# mainboard.net
KiCad netlist of a schematic drawn in Altium Designer
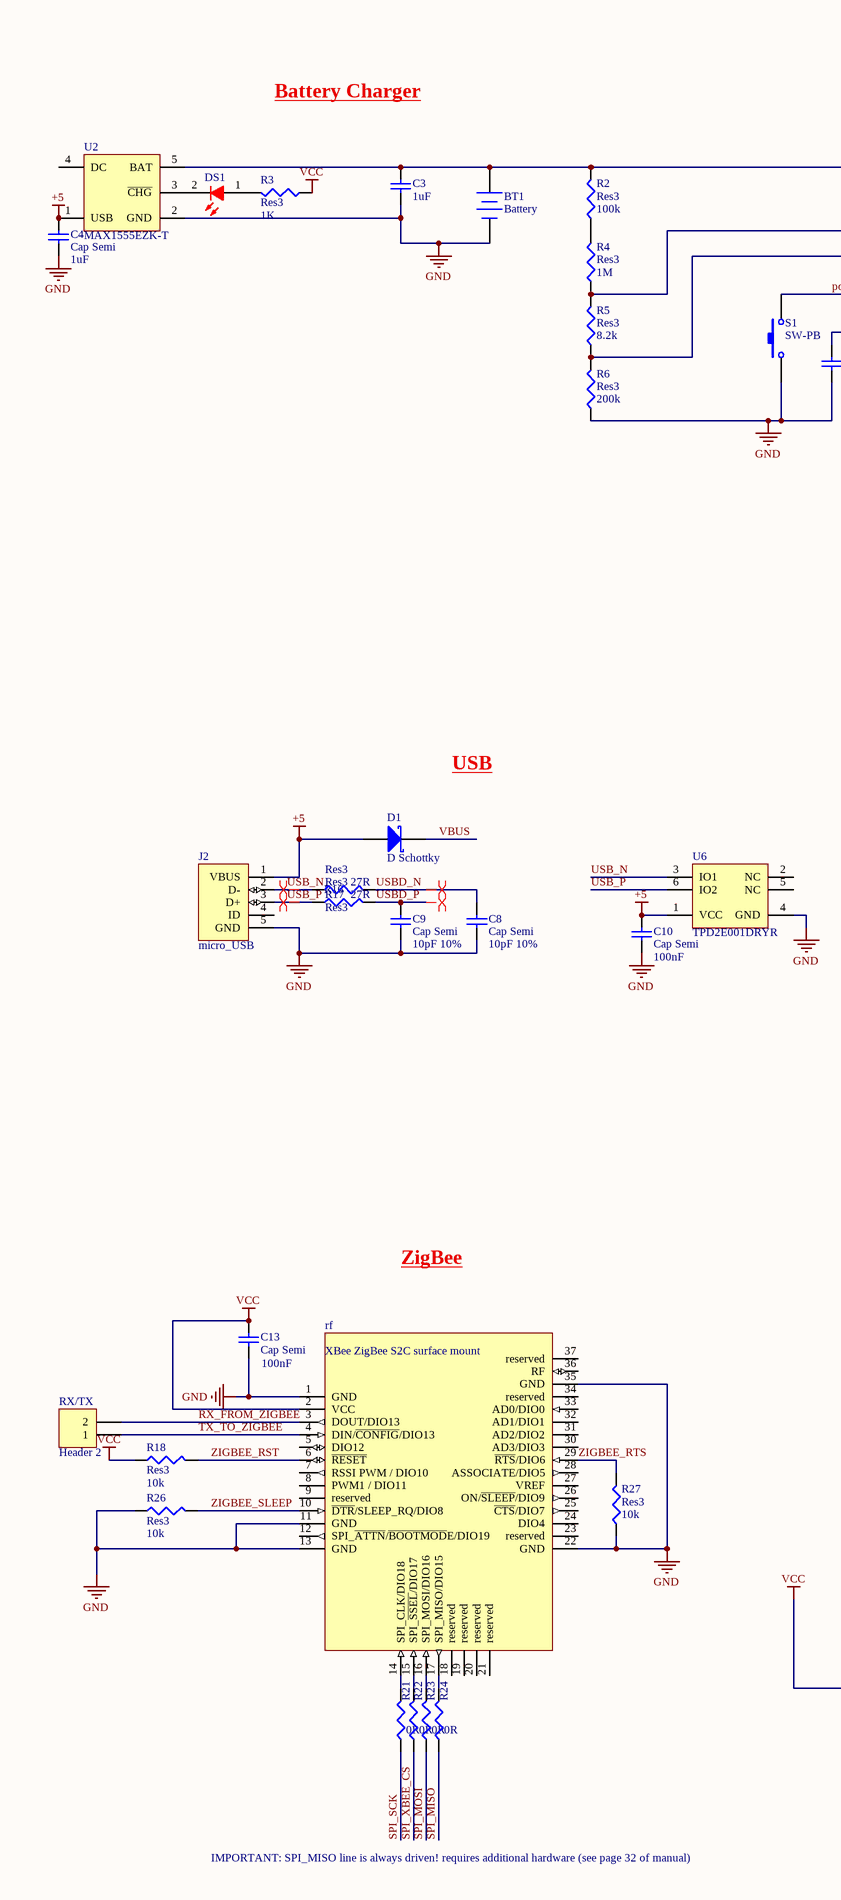
[diagram p0: mainboard.SchDoc, left]
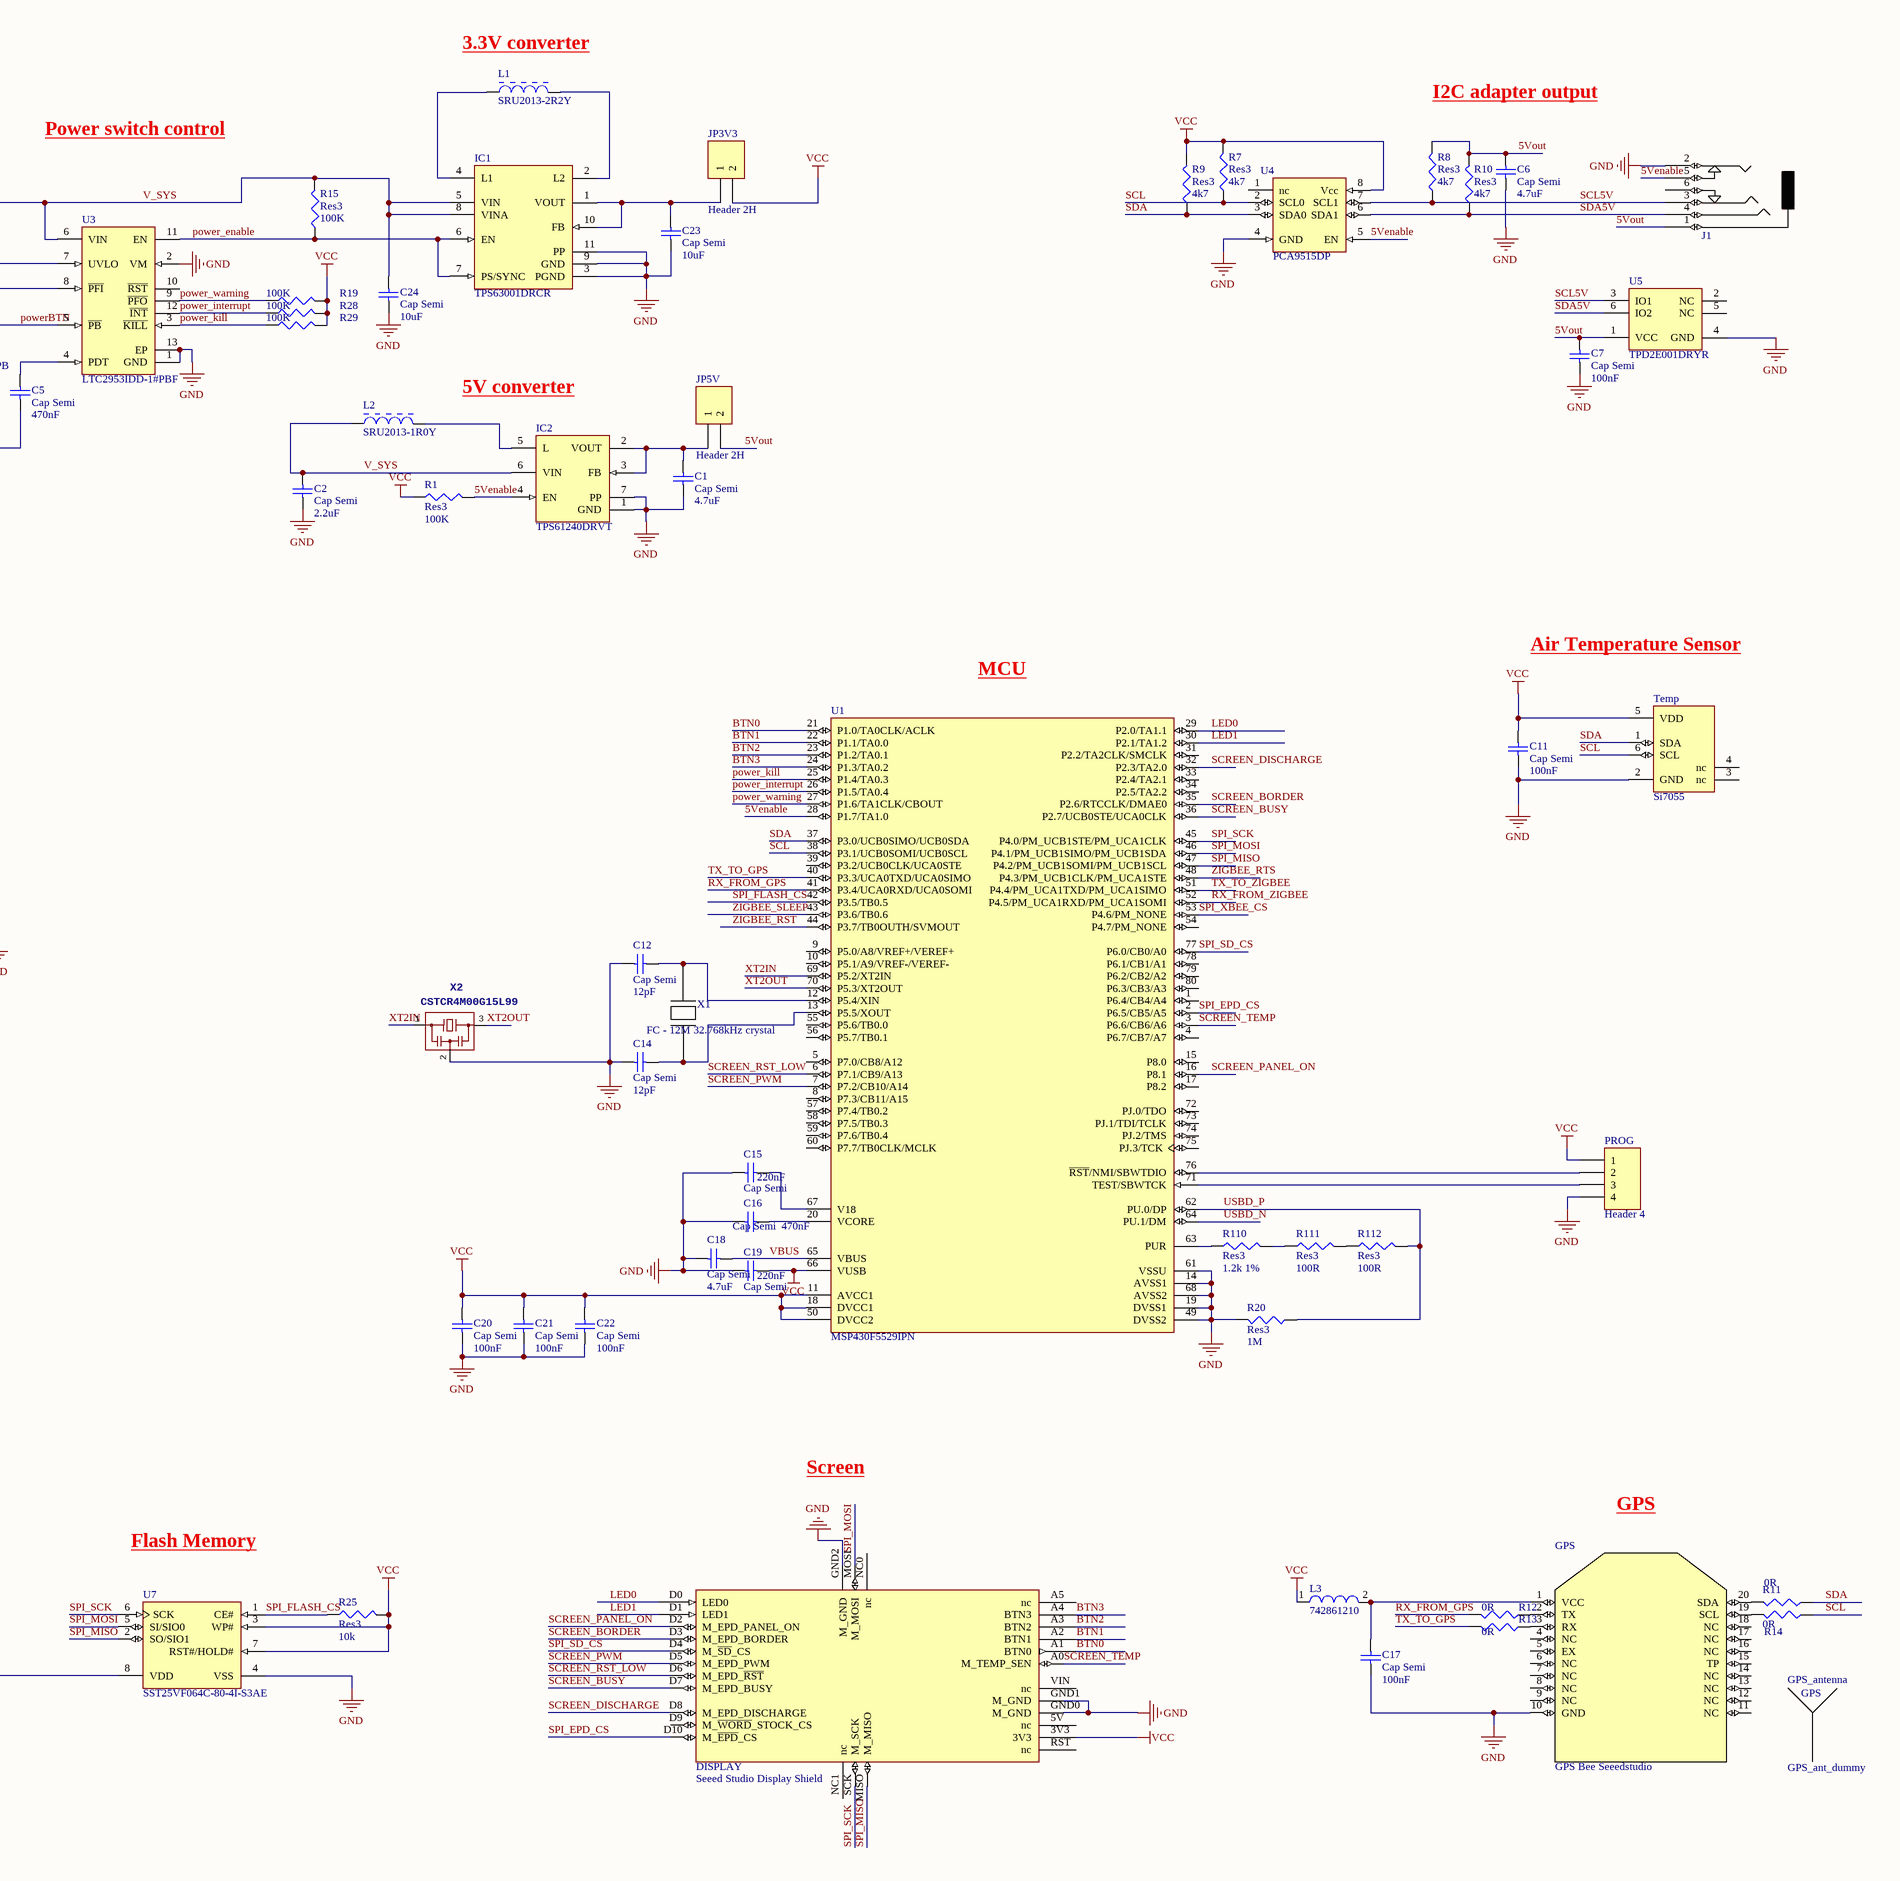
[diagram p1: mainboard.SchDoc, right]

(export (version "E")
  (design (tool "Eeschema 10.0.6"))
  (components
    (comp (ref "BT1")
      (value "Battery")
      (footprint "BAT-2")
      (description "Multicell Battery")
      (fields (field (name "PUBLISHER") "Altium Limited"))
      (libsource (lib "Miscellaneous Devices") (part "Battery"))
    )
    (comp (ref "C1")
      (value "Cap Semi")
      (footprint "1608[0603]")
      (description "Capacitor (Semiconductor SIM Model)")
      (fields (field (name "ALTIUM_VALUE") "4.7uF") (field (name "PUBLISHER") "Altium Limited"))
      (libsource (lib "Miscellaneous Devices") (part "Cap Semi"))
    )
    (comp (ref "C2")
      (value "Cap Semi")
      (footprint "1608[0603]")
      (description "Capacitor (Semiconductor SIM Model)")
      (fields (field (name "ALTIUM_VALUE") "2.2uF") (field (name "PUBLISHER") "Altium Limited"))
      (libsource (lib "Miscellaneous Devices") (part "Cap Semi"))
    )
    (comp (ref "C3")
      (value "1uF")
      (footprint "1608[0603]")
      (description "Capacitor (Semiconductor SIM Model)")
      (fields (field (name "Comment") "Cap Semi") (field (name "PUBLISHER") "Altium Limited"))
      (libsource (lib "Miscellaneous Devices") (part "Cap Semi"))
    )
    (comp (ref "C4")
      (value "Cap Semi")
      (footprint "1608[0603]")
      (description "Capacitor (Semiconductor SIM Model)")
      (fields (field (name "ALTIUM_VALUE") "1uF") (field (name "PUBLISHER") "Altium Limited"))
      (libsource (lib "Miscellaneous Devices") (part "Cap Semi"))
    )
    (comp (ref "C5")
      (value "Cap Semi")
      (footprint "1608[0603]")
      (description "Capacitor (Semiconductor SIM Model)")
      (fields (field (name "ALTIUM_VALUE") "470nF") (field (name "PUBLISHER") "Altium Limited"))
      (libsource (lib "Miscellaneous Devices") (part "Cap Semi"))
    )
    (comp (ref "C6")
      (value "Cap Semi")
      (footprint "1608[0603]")
      (description "Capacitor (Semiconductor SIM Model)")
      (fields (field (name "ALTIUM_VALUE") "4.7uF") (field (name "PUBLISHER") "Altium Limited"))
      (libsource (lib "Miscellaneous Devices") (part "Cap Semi"))
    )
    (comp (ref "C7")
      (value "Cap Semi")
      (footprint "1608[0603]")
      (description "Capacitor (Semiconductor SIM Model)")
      (fields (field (name "ALTIUM_VALUE") "100nF") (field (name "PUBLISHER") "Altium Limited"))
      (libsource (lib "Miscellaneous Devices") (part "Cap Semi"))
    )
    (comp (ref "C8")
      (value "Cap Semi")
      (footprint "1608[0603]")
      (description "Capacitor (Semiconductor SIM Model)")
      (fields (field (name "ALTIUM_VALUE") "10pF 10%") (field (name "PUBLISHER") "Altium Limited"))
      (libsource (lib "Miscellaneous Devices") (part "Cap Semi"))
    )
    (comp (ref "C9")
      (value "Cap Semi")
      (footprint "1608[0603]")
      (description "Capacitor (Semiconductor SIM Model)")
      (fields (field (name "ALTIUM_VALUE") "10pF 10%") (field (name "PUBLISHER") "Altium Limited"))
      (libsource (lib "Miscellaneous Devices") (part "Cap Semi"))
    )
    (comp (ref "C10")
      (value "Cap Semi")
      (footprint "1608[0603]")
      (description "Capacitor (Semiconductor SIM Model)")
      (fields (field (name "ALTIUM_VALUE") "100nF") (field (name "PUBLISHER") "Altium Limited"))
      (libsource (lib "Miscellaneous Devices") (part "Cap Semi"))
    )
    (comp (ref "C11")
      (value "Cap Semi")
      (footprint "1608[0603]")
      (description "Capacitor (Semiconductor SIM Model)")
      (fields (field (name "ALTIUM_VALUE") "100nF") (field (name "PUBLISHER") "Altium Limited"))
      (libsource (lib "Miscellaneous Devices") (part "Cap Semi"))
    )
    (comp (ref "C12")
      (value "Cap Semi")
      (footprint "1608[0603]")
      (description "Capacitor (Semiconductor SIM Model)")
      (fields (field (name "ALTIUM_VALUE") "12pF") (field (name "PUBLISHER") "Altium Limited"))
      (libsource (lib "Miscellaneous Devices") (part "Cap Semi"))
    )
    (comp (ref "C13")
      (value "Cap Semi")
      (footprint "1608[0603]")
      (description "Capacitor (Semiconductor SIM Model)")
      (fields (field (name "ALTIUM_VALUE") "100nF") (field (name "PUBLISHER") "Altium Limited"))
      (libsource (lib "Miscellaneous Devices") (part "Cap Semi"))
    )
    (comp (ref "C14")
      (value "Cap Semi")
      (footprint "1608[0603]")
      (description "Capacitor (Semiconductor SIM Model)")
      (fields (field (name "ALTIUM_VALUE") "12pF") (field (name "PUBLISHER") "Altium Limited"))
      (libsource (lib "Miscellaneous Devices") (part "Cap Semi"))
    )
    (comp (ref "C15")
      (value "Cap Semi")
      (footprint "1608[0603]")
      (description "Capacitor (Semiconductor SIM Model)")
      (fields (field (name "ALTIUM_VALUE") "220nF") (field (name "PUBLISHER") "Altium Limited"))
      (libsource (lib "Miscellaneous Devices") (part "Cap Semi"))
    )
    (comp (ref "C16")
      (value "Cap Semi")
      (footprint "1608[0603]")
      (description "Capacitor (Semiconductor SIM Model)")
      (fields (field (name "ALTIUM_VALUE") "470nF") (field (name "PUBLISHER") "Altium Limited"))
      (libsource (lib "Miscellaneous Devices") (part "Cap Semi"))
    )
    (comp (ref "C17")
      (value "Cap Semi")
      (footprint "1608[0603]")
      (description "Capacitor (Semiconductor SIM Model)")
      (fields (field (name "ALTIUM_VALUE") "100nF") (field (name "PUBLISHER") "Altium Limited"))
      (libsource (lib "Miscellaneous Devices") (part "Cap Semi"))
    )
    (comp (ref "C18")
      (value "Cap Semi")
      (footprint "1608[0603]")
      (description "Capacitor (Semiconductor SIM Model)")
      (fields (field (name "ALTIUM_VALUE") "4.7uF") (field (name "PUBLISHER") "Altium Limited"))
      (libsource (lib "Miscellaneous Devices") (part "Cap Semi"))
    )
    (comp (ref "C19")
      (value "Cap Semi")
      (footprint "1608[0603]")
      (description "Capacitor (Semiconductor SIM Model)")
      (fields (field (name "ALTIUM_VALUE") "220nF") (field (name "PUBLISHER") "Altium Limited"))
      (libsource (lib "Miscellaneous Devices") (part "Cap Semi"))
    )
    (comp (ref "C20")
      (value "Cap Semi")
      (footprint "1608[0603]")
      (description "Capacitor (Semiconductor SIM Model)")
      (fields (field (name "ALTIUM_VALUE") "100nF") (field (name "PUBLISHER") "Altium Limited"))
      (libsource (lib "Miscellaneous Devices") (part "Cap Semi"))
    )
    (comp (ref "C21")
      (value "Cap Semi")
      (footprint "1608[0603]")
      (description "Capacitor (Semiconductor SIM Model)")
      (fields (field (name "ALTIUM_VALUE") "100nF") (field (name "PUBLISHER") "Altium Limited"))
      (libsource (lib "Miscellaneous Devices") (part "Cap Semi"))
    )
    (comp (ref "C22")
      (value "Cap Semi")
      (footprint "1608[0603]")
      (description "Capacitor (Semiconductor SIM Model)")
      (fields (field (name "ALTIUM_VALUE") "100nF") (field (name "PUBLISHER") "Altium Limited"))
      (libsource (lib "Miscellaneous Devices") (part "Cap Semi"))
    )
    (comp (ref "C23")
      (value "Cap Semi")
      (footprint "C1206")
      (description "Capacitor (Semiconductor SIM Model)")
      (fields (field (name "ALTIUM_VALUE") "10uF") (field (name "PUBLISHER") "Altium Limited"))
      (libsource (lib "Miscellaneous Devices") (part "Cap Semi"))
    )
    (comp (ref "C24")
      (value "Cap Semi")
      (footprint "C1206")
      (description "Capacitor (Semiconductor SIM Model)")
      (fields (field (name "ALTIUM_VALUE") "10uF") (field (name "PUBLISHER") "Altium Limited"))
      (libsource (lib "Miscellaneous Devices") (part "Cap Semi"))
    )
    (comp (ref "D1")
      (value "D Schottky")
      (footprint "SMB")
      (description "Schottky Diode")
      (fields (field (name "PUBLISHER") "Altium Limited"))
      (libsource (lib "Miscellaneous Devices") (part "D Schottky"))
    )
    (comp (ref "DISPLAY")
      (value "Seeed Studio Display Shield")
      (footprint "Display shield")
      (libsource (lib "dorySchlib") (part "Seeed Studio Display Shield"))
    )
    (comp (ref "DS1")
      (value "TLSU1008A(T04)")
      (footprint "TOSH-0603LED_RED_V")
      (description "LED, Red 0603 (1608) 63mCd")
      (fields (field (name "MANUFACTURER") "Toshiba"))
      (libsource (lib "Altium Content Vault") (part "TOSH-LED-RED-A1K2-2"))
    )
    (comp (ref "GPS")
      (value "GPS Bee Seeedstudio")
      (footprint "GPS bee")
      (libsource (lib "dorySchlib") (part "GPS Bee Seeedstudio"))
    )
    (comp (ref "GPS_antenna")
      (value "GPS_ant_dummy")
      (footprint "GPS_ant_dummy")
      (libsource (lib "dorySchlib") (part "GPS_ant_dummy"))
    )
    (comp (ref "IC1")
      (value "TPS63001DRCR")
      (footprint "DRC10-2400X1650TP")
      (fields (field (name "MANUFACTURER") "Texas Instruments"))
      (libsource (lib "Altium Content Vault") (part "TI-TPS63001DRC10-3000X1650TP"))
    )
    (comp (ref "IC2")
      (value "TPS61240DRVT")
      (footprint "DRV6-1600X1000TP")
      (fields (field (name "MANUFACTURER") "Texas Instruments"))
      (libsource (lib "Altium Content Vault") (part "TI-TPS61240DRV6-1600X1000TP"))
    )
    (comp (ref "J1")
      (value "Jack_6")
      (footprint "Jack_6_socket")
      (description "4 pin 6 contact headphone jack 3.5mm")
      (libsource (lib "dorySchlib") (part "Jack_6"))
    )
    (comp (ref "J2")
      (value "micro_USB")
      (footprint "DX4RNW5HJ3")
      (fields (field (name "PARTNUMBER") "ZX62D-AB-5P8") (field (name "MANUFACTURER") "Hirose Electric"))
      (libsource (lib "dorySchlib") (part "micro_USB"))
    )
    (comp (ref "JP3V3")
      (value "Header 2H")
      (footprint "HDR1X2H")
      (description "Header, 2-Pin, Right Angle")
      (fields (field (name "PUBLISHER") "Altium Limited"))
      (libsource (lib "Miscellaneous Connectors") (part "Header 2H"))
    )
    (comp (ref "JP5V")
      (value "Header 2H")
      (footprint "HDR1X2H")
      (description "Header, 2-Pin, Right Angle")
      (fields (field (name "PUBLISHER") "Altium Limited"))
      (libsource (lib "Miscellaneous Connectors") (part "Header 2H"))
    )
    (comp (ref "L1")
      (value "SRU2013-2R2Y")
      (footprint "BOUR-SRU2013-2R2Y-2_V")
      (description "Power Inductor, 2.2 µH, 1.45 Irms Max(A), SMD")
      (fields (field (name "TOLERANCE") "+/-30%") (field (name "MANUFACTURER") "Bourns"))
      (libsource (lib "Altium Content Vault") (part "BOUR-SRU2013-2R2Y-2"))
    )
    (comp (ref "L2")
      (value "SRU2013-1R0Y")
      (footprint "BOUR-SRU2013-2R2Y-2_V")
      (description "Power Inductor, 2.2 µH, 1.45 Irms Max(A), SMD")
      (fields (field (name "TOLERANCE") "+/-30%") (field (name "PARTNUMBER") "SRU2013-2R2Y"))
      (libsource (lib "Altium Content Vault") (part "CMP-0462-00001-2"))
    )
    (comp (ref "L3")
      (value "742861210")
      (footprint "SMD-0603")
      (description "SMD EMI Suppression Ferrite Bead WE-CBF HF, Z = 1000 Ohm")
      (libsource (lib "Altium Content Vault") (part "PAS-IND-INDUCTOR-2"))
    )
    (comp (ref "PROG")
      (value "Header 4")
      (footprint "HDR1X4")
      (description "Header, 4-Pin")
      (fields (field (name "PUBLISHER") "Altium Limited"))
      (libsource (lib "Miscellaneous Connectors") (part "Header 4"))
    )
    (comp (ref "R1")
      (value "Res3")
      (footprint "J1-0603")
      (description "Resistor")
      (fields (field (name "ALTIUM_VALUE") "100K") (field (name "PUBLISHER") "Altium Limited"))
      (libsource (lib "Miscellaneous Devices") (part "Res3"))
    )
    (comp (ref "R2")
      (value "Res3")
      (footprint "J1-0603")
      (description "Resistor")
      (fields (field (name "ALTIUM_VALUE") "100k") (field (name "PUBLISHER") "Altium Limited"))
      (libsource (lib "Miscellaneous Devices") (part "Res3"))
    )
    (comp (ref "R3")
      (value "Res3")
      (footprint "J1-0603")
      (description "Resistor")
      (fields (field (name "ALTIUM_VALUE") "1K") (field (name "PUBLISHER") "Altium Limited"))
      (libsource (lib "Miscellaneous Devices") (part "Res3"))
    )
    (comp (ref "R4")
      (value "Res3")
      (footprint "J1-0603")
      (description "Resistor")
      (fields (field (name "ALTIUM_VALUE") "1M") (field (name "PUBLISHER") "Altium Limited"))
      (libsource (lib "Miscellaneous Devices") (part "Res3"))
    )
    (comp (ref "R5")
      (value "Res3")
      (footprint "J1-0603")
      (description "Resistor")
      (fields (field (name "ALTIUM_VALUE") "8.2k") (field (name "PUBLISHER") "Altium Limited"))
      (libsource (lib "Miscellaneous Devices") (part "Res3"))
    )
    (comp (ref "R6")
      (value "Res3")
      (footprint "J1-0603")
      (description "Resistor")
      (fields (field (name "ALTIUM_VALUE") "200k") (field (name "PUBLISHER") "Altium Limited"))
      (libsource (lib "Miscellaneous Devices") (part "Res3"))
    )
    (comp (ref "R7")
      (value "Res3")
      (footprint "J1-0603")
      (description "Resistor")
      (fields (field (name "ALTIUM_VALUE") "4k7") (field (name "PUBLISHER") "Altium Limited"))
      (libsource (lib "Miscellaneous Devices") (part "Res3"))
    )
    (comp (ref "R8")
      (value "Res3")
      (footprint "J1-0603")
      (description "Resistor")
      (fields (field (name "ALTIUM_VALUE") "4k7") (field (name "PUBLISHER") "Altium Limited"))
      (libsource (lib "Miscellaneous Devices") (part "Res3"))
    )
    (comp (ref "R9")
      (value "Res3")
      (footprint "J1-0603")
      (description "Resistor")
      (fields (field (name "ALTIUM_VALUE") "4k7") (field (name "PUBLISHER") "Altium Limited"))
      (libsource (lib "Miscellaneous Devices") (part "Res3"))
    )
    (comp (ref "R10")
      (value "Res3")
      (footprint "J1-0603")
      (description "Resistor")
      (fields (field (name "ALTIUM_VALUE") "4k7") (field (name "PUBLISHER") "Altium Limited"))
      (libsource (lib "Miscellaneous Devices") (part "Res3"))
    )
    (comp (ref "R11")
      (value "0R")
      (footprint "J1-0603")
      (description "Resistor")
      (fields (field (name "Comment") "Res3") (field (name "PUBLISHER") "Altium Limited"))
      (libsource (lib "Miscellaneous Devices") (part "Res3"))
    )
    (comp (ref "R12")
      (value "0R")
      (footprint "J1-0603")
      (description "Resistor")
      (fields (field (name "Comment") "Res3") (field (name "PUBLISHER") "Altium Limited"))
      (libsource (lib "Miscellaneous Devices") (part "Res3"))
    )
    (comp (ref "R13")
      (value "0R")
      (footprint "J1-0603")
      (description "Resistor")
      (fields (field (name "Comment") "Res3") (field (name "PUBLISHER") "Altium Limited"))
      (libsource (lib "Miscellaneous Devices") (part "Res3"))
    )
    (comp (ref "R14")
      (value "0R")
      (footprint "J1-0603")
      (description "Resistor")
      (fields (field (name "Comment") "Res3") (field (name "PUBLISHER") "Altium Limited"))
      (libsource (lib "Miscellaneous Devices") (part "Res3"))
    )
    (comp (ref "R15")
      (value "Res3")
      (footprint "J1-0603")
      (description "Resistor")
      (fields (field (name "ALTIUM_VALUE") "100K") (field (name "PUBLISHER") "Altium Limited"))
      (libsource (lib "Miscellaneous Devices") (part "Res3"))
    )
    (comp (ref "R16")
      (value "Res3")
      (footprint "J1-0603")
      (description "Resistor")
      (fields
        (field (name "ALTIUM_VALUE") "27R")
        (field (name "COMMENT_1") "Res3")
        (field (name "PUBLISHER") "Altium Limited")
      )
      (libsource (lib "Miscellaneous Devices") (part "Res3"))
    )
    (comp (ref "R17")
      (value "Res3")
      (footprint "J1-0603")
      (description "Resistor")
      (fields (field (name "ALTIUM_VALUE") "27R") (field (name "PUBLISHER") "Altium Limited"))
      (libsource (lib "Miscellaneous Devices") (part "Res3"))
    )
    (comp (ref "R18")
      (value "Res3")
      (footprint "J1-0603")
      (description "Resistor")
      (fields (field (name "ALTIUM_VALUE") "10k") (field (name "PUBLISHER") "Altium Limited"))
      (libsource (lib "Miscellaneous Devices") (part "Res3"))
    )
    (comp (ref "R19")
      (value "100K")
      (footprint "J1-0603")
      (description "Resistor")
      (fields (field (name "Comment") "Res3") (field (name "PUBLISHER") "Altium Limited"))
      (libsource (lib "Miscellaneous Devices") (part "Res3"))
    )
    (comp (ref "R20")
      (value "Res3")
      (footprint "J1-0603")
      (description "Resistor")
      (fields (field (name "ALTIUM_VALUE") "1M") (field (name "PUBLISHER") "Altium Limited"))
      (libsource (lib "Miscellaneous Devices") (part "Res3"))
    )
    (comp (ref "R21")
      (value "0R")
      (footprint "J1-0603")
      (description "Resistor")
      (fields (field (name "Comment") "Res3") (field (name "PUBLISHER") "Altium Limited"))
      (libsource (lib "Miscellaneous Devices") (part "Res3"))
    )
    (comp (ref "R22")
      (value "0R")
      (footprint "J1-0603")
      (description "Resistor")
      (fields (field (name "Comment") "Res3") (field (name "PUBLISHER") "Altium Limited"))
      (libsource (lib "Miscellaneous Devices") (part "Res3"))
    )
    (comp (ref "R23")
      (value "0R")
      (footprint "J1-0603")
      (description "Resistor")
      (fields (field (name "Comment") "Res3") (field (name "PUBLISHER") "Altium Limited"))
      (libsource (lib "Miscellaneous Devices") (part "Res3"))
    )
    (comp (ref "R24")
      (value "0R")
      (footprint "J1-0603")
      (description "Resistor")
      (fields (field (name "Comment") "Res3") (field (name "PUBLISHER") "Altium Limited"))
      (libsource (lib "Miscellaneous Devices") (part "Res3"))
    )
    (comp (ref "R25")
      (value "Res3")
      (footprint "J1-0603")
      (description "Resistor")
      (fields (field (name "ALTIUM_VALUE") "10k") (field (name "PUBLISHER") "Altium Limited"))
      (libsource (lib "Miscellaneous Devices") (part "Res3"))
    )
    (comp (ref "R26")
      (value "Res3")
      (footprint "J1-0603")
      (description "Resistor")
      (fields (field (name "ALTIUM_VALUE") "10k") (field (name "PUBLISHER") "Altium Limited"))
      (libsource (lib "Miscellaneous Devices") (part "Res3"))
    )
    (comp (ref "R27")
      (value "Res3")
      (footprint "J1-0603")
      (description "Resistor")
      (fields (field (name "ALTIUM_VALUE") "10k") (field (name "PUBLISHER") "Altium Limited"))
      (libsource (lib "Miscellaneous Devices") (part "Res3"))
    )
    (comp (ref "R28")
      (value "100K")
      (footprint "J1-0603")
      (description "Resistor")
      (fields (field (name "Comment") "Res3") (field (name "PUBLISHER") "Altium Limited"))
      (libsource (lib "Miscellaneous Devices") (part "Res3"))
    )
    (comp (ref "R29")
      (value "100K")
      (footprint "J1-0603")
      (description "Resistor")
      (fields (field (name "Comment") "Res3") (field (name "PUBLISHER") "Altium Limited"))
      (libsource (lib "Miscellaneous Devices") (part "Res3"))
    )
    (comp (ref "R110")
      (value "Res3")
      (footprint "J1-0603")
      (description "Resistor")
      (fields (field (name "ALTIUM_VALUE") "1.2k 1%") (field (name "PUBLISHER") "Altium Limited"))
      (libsource (lib "Miscellaneous Devices") (part "Res3"))
    )
    (comp (ref "R111")
      (value "Res3")
      (footprint "J1-0603")
      (description "Resistor")
      (fields (field (name "ALTIUM_VALUE") "100R") (field (name "PUBLISHER") "Altium Limited"))
      (libsource (lib "Miscellaneous Devices") (part "Res3"))
    )
    (comp (ref "R112")
      (value "Res3")
      (footprint "J1-0603")
      (description "Resistor")
      (fields (field (name "ALTIUM_VALUE") "100R") (field (name "PUBLISHER") "Altium Limited"))
      (libsource (lib "Miscellaneous Devices") (part "Res3"))
    )
    (comp (ref "rf")
      (value "XBee ZigBee S2C surface mount")
      (footprint "S2C XBEE")
      (libsource (lib "dorySchlib") (part "XBee ZigBee S2C surface mount"))
    )
    (comp (ref "RX/TX")
      (value "Header 2")
      (footprint "HDR1X2")
      (description "Header, 2-Pin")
      (fields (field (name "PUBLISHER") "Altium Limited"))
      (libsource (lib "Miscellaneous Connectors") (part "Header 2"))
    )
    (comp (ref "S1")
      (value "SW-PB")
      (footprint "SPST-2")
      (description "Switch")
      (fields (field (name "PUBLISHER") "Altium Limited"))
      (libsource (lib "Miscellaneous Devices") (part "SW-PB"))
    )
    (comp (ref "Temp")
      (value "Si7055")
      (footprint "Si7050/3/4/5")
      (libsource (lib "dorySchlib") (part "Si7055"))
    )
    (comp (ref "U1")
      (value "MSP430F5529IPN")
      (footprint "TI-PN80_N")
      (fields (field (name "MANUFACTURER") "Texas Instruments"))
      (libsource (lib "Altium Content Vault") (part "CMP-0365-00412-1"))
    )
    (comp (ref "U2")
      (value "MAX1555EZK-T")
      (footprint "MAXM-Z5-1_N")
      (fields (field (name "MANUFACTURER") "Maxim"))
      (libsource (lib "Altium Content Vault") (part "MAXM-MAX1555-Z5-1"))
    )
    (comp (ref "U3")
      (value "LTC2953IDD-1#PBF")
      (footprint "LT-DD-12_V")
      (fields (field (name "MANUFACTURER") "Linear Technology"))
      (libsource (lib "Altium Content Vault") (part "LT-LTC2953-1-DD-12"))
    )
    (comp (ref "U4")
      (value "PCA9515DP")
      (footprint "TSOP65P490X110-8N")
      (description "PCA9515 I2C logic level converter")
      (libsource (lib "dorySchlib") (part "PCA9515DP"))
    )
    (comp (ref "U5")
      (value "TPD2E001DRYR")
      (footprint "DRY6")
      (fields (field (name "MANUFACTURER") "Texas Instruments"))
      (libsource (lib "dorySchlib") (part "TI-TPD2E001-SON_DRY-6"))
    )
    (comp (ref "U6")
      (value "TPD2E001DRYR")
      (footprint "DRY6")
      (fields (field (name "MANUFACTURER") "Texas Instruments"))
      (libsource (lib "dorySchlib") (part "TI-TPD2E001-SON_DRY-6"))
    )
    (comp (ref "U7")
      (value "SST25VF064C-80-4I-S3AE")
      (footprint "MCHP-SOIC-S3A8_M")
      (description "64 Mbit SPI Serial Flash, 2.7 to 3.6 V, 80 MHz, -40 to 85 degC, 8-pin SOIC (S3A8), Tube")
      (fields (field (name "MANUFACTURER") "Microchip"))
      (libsource (lib "Altium Content Vault") (part "MCHP-SST25VF064C-SOIJ-S-8"))
    )
    (comp (ref "X1")
      (value "FC - 12M 32.768kHz crystal")
      (footprint "FC-12M")
      (description "Epson FC - 12M")
      (libsource (lib "dorySchlib") (part "FC - 12M 32.768kHz crystal"))
    )
    (comp (ref "X2")
      (value "CSTCR4M00G15L99")
      (footprint "CSTCR_G15L")
      (description "<b>Resonator</b><p>\nSource: murata.co.jp")
      (libsource (lib "murata") (part "MURATA-FILTER_CSTCR"))
    )
  )
  (nets
    (net (code "1") (name "+5") (class "Default")
      (node (ref "C10") (pin "2") (pinfunction "2_2") (pintype "passive"))
      (node (ref "C4") (pin "2") (pinfunction "2_2") (pintype "passive"))
      (node (ref "D1") (pin "1") (pinfunction "A_1") (pintype "passive"))
      (node (ref "J2") (pin "1") (pinfunction "VBUS_1") (pintype "power_in"))
      (node (ref "U2") (pin "1") (pinfunction "USB_1") (pintype "power_in"))
      (node (ref "U6") (pin "1") (pinfunction "VCC_1") (pintype "power_in"))
    )
    (net (code "2") (name "/5Venable") (class "Default")
      (node (ref "IC2") (pin "4") (pinfunction "EN_4") (pintype "input"))
      (node (ref "J1") (pin "5") (pinfunction "tip_switch_5") (pintype "bidirectional"))
      (node (ref "R1") (pin "2") (pinfunction "2_2") (pintype "passive"))
      (node (ref "U1") (pin "28") (pinfunction "P1.7/TA1.0_28") (pintype "bidirectional"))
      (node (ref "U4") (pin "5") (pinfunction "EN_5") (pintype "input"))
    )
    (net (code "3") (name "/5Vout") (class "Default")
      (node (ref "C6") (pin "2") (pinfunction "2_2") (pintype "passive"))
      (node (ref "C7") (pin "2") (pinfunction "2_2") (pintype "passive"))
      (node (ref "J1") (pin "1") (pinfunction "sleeve_1") (pintype "bidirectional"))
      (node (ref "JP5V") (pin "2") (pinfunction "2_2") (pintype "passive"))
      (node (ref "R10") (pin "2") (pinfunction "2_2") (pintype "passive"))
      (node (ref "R8") (pin "2") (pinfunction "2_2") (pintype "passive"))
      (node (ref "U5") (pin "1") (pinfunction "VCC_1") (pintype "power_in"))
    )
    (net (code "4") (name "/BTN0") (class "Default")
      (node (ref "DISPLAY") (pin "A1") (pinfunction "BTN0_A1") (pintype "output"))
      (node (ref "U1") (pin "21") (pinfunction "P1.0/TA0CLK/ACLK_21") (pintype "bidirectional"))
    )
    (net (code "5") (name "/BTN1") (class "Default")
      (node (ref "DISPLAY") (pin "A2") (pinfunction "BTN1_A2") (pintype "passive"))
      (node (ref "U1") (pin "22") (pinfunction "P1.1/TA0.0_22") (pintype "bidirectional"))
    )
    (net (code "6") (name "/BTN2") (class "Default")
      (node (ref "DISPLAY") (pin "A3") (pinfunction "BTN2_A3") (pintype "passive"))
      (node (ref "U1") (pin "23") (pinfunction "P1.2/TA0.1_23") (pintype "bidirectional"))
    )
    (net (code "7") (name "/BTN3") (class "Default")
      (node (ref "DISPLAY") (pin "A4") (pinfunction "BTN3_A4") (pintype "passive"))
      (node (ref "U1") (pin "24") (pinfunction "P1.3/TA0.2_24") (pintype "bidirectional"))
    )
    (net (code "8") (name "/LED0") (class "Default")
      (node (ref "DISPLAY") (pin "D0") (pinfunction "LED0_D0") (pintype "input"))
      (node (ref "U1") (pin "29") (pinfunction "P2.0/TA1.1_29") (pintype "bidirectional"))
    )
    (net (code "9") (name "/LED1") (class "Default")
      (node (ref "DISPLAY") (pin "D1") (pinfunction "LED1_D1") (pintype "input"))
      (node (ref "U1") (pin "30") (pinfunction "P2.1/TA1.2_30") (pintype "bidirectional"))
    )
    (net (code "10") (name "/RX_FROM_GPS") (class "Default")
      (node (ref "R12") (pin "2") (pinfunction "2_2") (pintype "passive"))
      (node (ref "U1") (pin "41") (pinfunction "P3.4/UCA0RXD/UCA0SOMI_41") (pintype "bidirectional"))
    )
    (net (code "11") (name "/RX_FROM_ZIGBEE") (class "Default")
      (node (ref "RX/TX") (pin "2") (pinfunction "2_2") (pintype "passive"))
      (node (ref "U1") (pin "52") (pinfunction "P4.5/PM_UCA1RXD/PM_UCA1SOMI_52") (pintype "bidirectional"))
      (node (ref "rf") (pin "3") (pinfunction "DOUT/DIO13_3") (pintype "output"))
    )
    (net (code "12") (name "/SCL") (class "Default")
      (node (ref "R14") (pin "1") (pinfunction "1_1") (pintype "passive"))
      (node (ref "R7") (pin "1") (pinfunction "1_1") (pintype "passive"))
      (node (ref "Temp") (pin "6") (pinfunction "SCL_6") (pintype "bidirectional"))
      (node (ref "U1") (pin "38") (pinfunction "P3.1/UCB0SOMI/UCB0SCL_38") (pintype "bidirectional"))
      (node (ref "U4") (pin "2") (pinfunction "SCL0_2") (pintype "bidirectional"))
    )
    (net (code "13") (name "/SCL5V") (class "Default")
      (node (ref "J1") (pin "3") (pinfunction "ring_1_3") (pintype "bidirectional"))
      (node (ref "R8") (pin "1") (pinfunction "1_1") (pintype "passive"))
      (node (ref "U4") (pin "7") (pinfunction "SCL1_7") (pintype "bidirectional"))
      (node (ref "U5") (pin "3") (pinfunction "IO1_3") (pintype "passive"))
    )
    (net (code "14") (name "/SCREEN_BORDER") (class "Default")
      (node (ref "DISPLAY") (pin "D3") (pinfunction "M_EPD_BORDER_D3") (pintype "bidirectional"))
      (node (ref "U1") (pin "35") (pinfunction "P2.6/RTCCLK/DMAE0_35") (pintype "bidirectional"))
    )
    (net (code "15") (name "/SCREEN_BUSY") (class "Default")
      (node (ref "DISPLAY") (pin "D7") (pinfunction "M_EPD_BUSY_D7") (pintype "bidirectional"))
      (node (ref "U1") (pin "36") (pinfunction "P2.7/UCB0STE/UCA0CLK_36") (pintype "bidirectional"))
    )
    (net (code "16") (name "/SCREEN_DISCHARGE") (class "Default")
      (node (ref "DISPLAY") (pin "D8") (pinfunction "M_EPD_DISCHARGE_D8") (pintype "bidirectional"))
      (node (ref "U1") (pin "32") (pinfunction "P2.3/TA2.0_32") (pintype "bidirectional"))
    )
    (net (code "17") (name "/SCREEN_PANEL_ON") (class "Default")
      (node (ref "DISPLAY") (pin "D2") (pinfunction "M_EPD_PANEL_ON_D2") (pintype "bidirectional"))
      (node (ref "U1") (pin "16") (pinfunction "P8.1_16") (pintype "bidirectional"))
    )
    (net (code "18") (name "/SCREEN_PWM") (class "Default")
      (node (ref "DISPLAY") (pin "D5") (pinfunction "M_EPD_PWM_D5") (pintype "bidirectional"))
      (node (ref "U1") (pin "7") (pinfunction "P7.2/CB10/A14_7") (pintype "bidirectional"))
    )
    (net (code "19") (name "/SCREEN_RST_LOW") (class "Default")
      (node (ref "DISPLAY") (pin "D6") (pinfunction "M_EPD_~{RST}_D6") (pintype "bidirectional"))
      (node (ref "U1") (pin "6") (pinfunction "P7.1/CB9/A13_6") (pintype "bidirectional"))
    )
    (net (code "20") (name "/SCREEN_TEMP") (class "Default")
      (node (ref "DISPLAY") (pin "A0") (pinfunction "M_TEMP_SEN_A0") (pintype "bidirectional"))
      (node (ref "U1") (pin "3") (pinfunction "P6.6/CB6/A6_3") (pintype "bidirectional"))
    )
    (net (code "21") (name "/SDA") (class "Default")
      (node (ref "R11") (pin "1") (pinfunction "1_1") (pintype "passive"))
      (node (ref "R9") (pin "1") (pinfunction "1_1") (pintype "passive"))
      (node (ref "Temp") (pin "1") (pinfunction "SDA_1") (pintype "bidirectional"))
      (node (ref "U1") (pin "37") (pinfunction "P3.0/UCB0SIMO/UCB0SDA_37") (pintype "bidirectional"))
      (node (ref "U4") (pin "3") (pinfunction "SDA0_3") (pintype "bidirectional"))
    )
    (net (code "22") (name "/SDA5V") (class "Default")
      (node (ref "J1") (pin "4") (pinfunction "ring_2_4") (pintype "bidirectional"))
      (node (ref "R10") (pin "1") (pinfunction "1_1") (pintype "passive"))
      (node (ref "U4") (pin "6") (pinfunction "SDA1_6") (pintype "bidirectional"))
      (node (ref "U5") (pin "6") (pinfunction "IO2_6") (pintype "passive"))
    )
    (net (code "23") (name "/SPI_EPD_CS") (class "Default")
      (node (ref "DISPLAY") (pin "D10") (pinfunction "M_~{EPD}_CS_D10") (pintype "bidirectional"))
      (node (ref "U1") (pin "2") (pinfunction "P6.5/CB5/A5_2") (pintype "bidirectional"))
    )
    (net (code "24") (name "/SPI_FLASH_CS") (class "Default")
      (node (ref "R25") (pin "1") (pinfunction "1_1") (pintype "passive"))
      (node (ref "U1") (pin "42") (pinfunction "P3.5/TB0.5_42") (pintype "bidirectional"))
      (node (ref "U7") (pin "1") (pinfunction "CE#_1") (pintype "input"))
    )
    (net (code "25") (name "/SPI_MISO") (class "Default")
      (node (ref "DISPLAY") (pin "MISO") (pinfunction "M_MISO_MISO") (pintype "bidirectional"))
      (node (ref "R24") (pin "1") (pinfunction "1_1") (pintype "passive"))
      (node (ref "U1") (pin "47") (pinfunction "P4.2/PM_UCB1SOMI/PM_UCB1SCL_47") (pintype "bidirectional"))
      (node (ref "U7") (pin "2") (pinfunction "SO/SIO1_2") (pintype "bidirectional"))
    )
    (net (code "26") (name "/SPI_MOSI") (class "Default")
      (node (ref "DISPLAY") (pin "MOSI") (pinfunction "M_MOSI_MOSI") (pintype "bidirectional"))
      (node (ref "R23") (pin "1") (pinfunction "1_1") (pintype "passive"))
      (node (ref "U1") (pin "46") (pinfunction "P4.1/PM_UCB1SIMO/PM_UCB1SDA_46") (pintype "bidirectional"))
      (node (ref "U7") (pin "5") (pinfunction "SI/SIO0_5") (pintype "bidirectional"))
    )
    (net (code "27") (name "/SPI_SCK") (class "Default")
      (node (ref "DISPLAY") (pin "SCK") (pinfunction "M_SCK_SCK") (pintype "bidirectional"))
      (node (ref "R21") (pin "1") (pinfunction "1_1") (pintype "passive"))
      (node (ref "U1") (pin "45") (pinfunction "P4.0/PM_UCB1STE/PM_UCA1CLK_45") (pintype "bidirectional"))
      (node (ref "U7") (pin "6") (pinfunction "SCK_6") (pintype "input"))
    )
    (net (code "28") (name "/SPI_SD_CS") (class "Default")
      (node (ref "DISPLAY") (pin "D4") (pinfunction "M_~{SD}_CS_D4") (pintype "bidirectional"))
      (node (ref "U1") (pin "77") (pinfunction "P6.0/CB0/A0_77") (pintype "bidirectional"))
    )
    (net (code "29") (name "/SPI_XBEE_CS") (class "Default")
      (node (ref "R22") (pin "1") (pinfunction "1_1") (pintype "passive"))
      (node (ref "U1") (pin "53") (pinfunction "P4.6/PM_NONE_53") (pintype "bidirectional"))
    )
    (net (code "30") (name "/TX_TO_GPS") (class "Default")
      (node (ref "R13") (pin "2") (pinfunction "2_2") (pintype "passive"))
      (node (ref "U1") (pin "40") (pinfunction "P3.3/UCA0TXD/UCA0SIMO_40") (pintype "bidirectional"))
    )
    (net (code "31") (name "/TX_TO_ZIGBEE") (class "Default")
      (node (ref "RX/TX") (pin "1") (pinfunction "1_1") (pintype "passive"))
      (node (ref "U1") (pin "51") (pinfunction "P4.4/PM_UCA1TXD/PM_UCA1SIMO_51") (pintype "bidirectional"))
      (node (ref "rf") (pin "4") (pinfunction "DIN/~{CONFIG}/DIO13_4") (pintype "input"))
    )
    (net (code "32") (name "/USBD_N") (class "Default")
      (node (ref "C8") (pin "2") (pinfunction "2_2") (pintype "passive"))
      (node (ref "R17") (pin "2") (pinfunction "2_2") (pintype "passive"))
      (node (ref "U1") (pin "64") (pinfunction "PU.1/DM_64") (pintype "bidirectional"))
    )
    (net (code "33") (name "/USBD_P") (class "Default")
      (node (ref "C9") (pin "2") (pinfunction "2_2") (pintype "passive"))
      (node (ref "R112") (pin "2") (pinfunction "2_2") (pintype "passive"))
      (node (ref "R16") (pin "2") (pinfunction "2_2") (pintype "passive"))
      (node (ref "R20") (pin "1") (pinfunction "1_1") (pintype "passive"))
      (node (ref "U1") (pin "62") (pinfunction "PU.0/DP_62") (pintype "bidirectional"))
    )
    (net (code "34") (name "/USB_N") (class "Default")
      (node (ref "J2") (pin "2") (pinfunction "D-_2") (pintype "bidirectional"))
      (node (ref "R17") (pin "1") (pinfunction "1_1") (pintype "passive"))
      (node (ref "U6") (pin "3") (pinfunction "IO1_3") (pintype "passive"))
    )
    (net (code "35") (name "/USB_P") (class "Default")
      (node (ref "J2") (pin "3") (pinfunction "D+_3") (pintype "bidirectional"))
      (node (ref "R16") (pin "1") (pinfunction "1_1") (pintype "passive"))
      (node (ref "U6") (pin "6") (pinfunction "IO2_6") (pintype "passive"))
    )
    (net (code "36") (name "/VBUS") (class "Default")
      (node (ref "C18") (pin "2") (pinfunction "2_2") (pintype "passive"))
      (node (ref "D1") (pin "2") (pinfunction "K_2") (pintype "passive"))
      (node (ref "U1") (pin "65") (pinfunction "VBUS_65") (pintype "power_in"))
    )
    (net (code "37") (name "/V_SYS") (class "Default")
      (node (ref "BT1") (pin "1") (pinfunction "+_1") (pintype "passive"))
      (node (ref "C2") (pin "2") (pinfunction "2_2") (pintype "passive"))
      (node (ref "C24") (pin "1") (pinfunction "1_1") (pintype "passive"))
      (node (ref "C3") (pin "2") (pinfunction "2_2") (pintype "passive"))
      (node (ref "IC1") (pin "5") (pinfunction "VIN_5") (pintype "power_in"))
      (node (ref "IC1") (pin "8") (pinfunction "VINA_8") (pintype "power_in"))
      (node (ref "IC2") (pin "6") (pinfunction "VIN_6") (pintype "power_in"))
      (node (ref "L2") (pin "1") (pinfunction "1_1") (pintype "passive"))
      (node (ref "R15") (pin "2") (pinfunction "2_2") (pintype "passive"))
      (node (ref "R2") (pin "2") (pinfunction "2_2") (pintype "passive"))
      (node (ref "U2") (pin "5") (pinfunction "BAT_5") (pintype "power_in"))
      (node (ref "U3") (pin "6") (pinfunction "VIN_6") (pintype "power_in"))
    )
    (net (code "38") (name "/XT2IN") (class "Default")
      (node (ref "U1") (pin "69") (pinfunction "P5.2/XT2IN_69") (pintype "bidirectional"))
      (node (ref "X2") (pin "1") (pinfunction "1_1") (pintype "passive"))
    )
    (net (code "39") (name "/XT2OUT") (class "Default")
      (node (ref "U1") (pin "70") (pinfunction "P5.3/XT2OUT_70") (pintype "bidirectional"))
      (node (ref "X2") (pin "3") (pinfunction "3_3") (pintype "passive"))
    )
    (net (code "40") (name "/ZIGBEE_RST") (class "Default")
      (node (ref "R18") (pin "2") (pinfunction "2_2") (pintype "passive"))
      (node (ref "U1") (pin "44") (pinfunction "P3.7/TB0OUTH/SVMOUT_44") (pintype "bidirectional"))
      (node (ref "rf") (pin "6") (pinfunction "~{RESET}_6") (pintype "bidirectional"))
    )
    (net (code "41") (name "/ZIGBEE_RTS") (class "Default")
      (node (ref "R27") (pin "2") (pinfunction "2_2") (pintype "passive"))
      (node (ref "U1") (pin "48") (pinfunction "P4.3/PM_UCB1CLK/PM_UCA1STE_48") (pintype "bidirectional"))
      (node (ref "rf") (pin "29") (pinfunction "~{RTS}/DIO6_29") (pintype "input"))
    )
    (net (code "42") (name "/ZIGBEE_SLEEP") (class "Default")
      (node (ref "R26") (pin "2") (pinfunction "2_2") (pintype "passive"))
      (node (ref "U1") (pin "43") (pinfunction "P3.6/TB0.6_43") (pintype "bidirectional"))
      (node (ref "rf") (pin "10") (pinfunction "~{DTR}/SLEEP_RQ/DIO8_10") (pintype "input"))
    )
    (net (code "43") (name "/powerBTN") (class "Default")
      (node (ref "S1") (pin "2") (pinfunction "2_2") (pintype "passive"))
      (node (ref "U3") (pin "5") (pinfunction "~{PB}_5") (pintype "input"))
    )
    (net (code "44") (name "/power_enable") (class "Default")
      (node (ref "IC1") (pin "6") (pinfunction "EN_6") (pintype "input"))
      (node (ref "IC1") (pin "7") (pinfunction "PS/SYNC_7") (pintype "input"))
      (node (ref "R15") (pin "1") (pinfunction "1_1") (pintype "passive"))
      (node (ref "U3") (pin "11") (pinfunction "EN_11") (pintype "open_collector"))
    )
    (net (code "45") (name "/power_interrupt") (class "Default")
      (node (ref "R28") (pin "1") (pinfunction "1_1") (pintype "passive"))
      (node (ref "U1") (pin "26") (pinfunction "P1.5/TA0.4_26") (pintype "bidirectional"))
      (node (ref "U3") (pin "12") (pinfunction "~{INT}_12") (pintype "open_collector"))
    )
    (net (code "46") (name "/power_kill") (class "Default")
      (node (ref "R29") (pin "1") (pinfunction "1_1") (pintype "passive"))
      (node (ref "U1") (pin "25") (pinfunction "P1.4/TA0.3_25") (pintype "bidirectional"))
      (node (ref "U3") (pin "3") (pinfunction "~{KILL}_3") (pintype "input"))
    )
    (net (code "47") (name "/power_warning") (class "Default")
      (node (ref "R19") (pin "1") (pinfunction "1_1") (pintype "passive"))
      (node (ref "U1") (pin "27") (pinfunction "P1.6/TA1CLK/CBOUT_27") (pintype "bidirectional"))
      (node (ref "U3") (pin "9") (pinfunction "~{PFO}_9") (pintype "tri_state"))
    )
    (net (code "48") (name "GND") (class "Default")
      (node (ref "BT1") (pin "2") (pinfunction "-_2") (pintype "passive"))
      (node (ref "C1") (pin "1") (pinfunction "1_1") (pintype "passive"))
      (node (ref "C10") (pin "1") (pinfunction "1_1") (pintype "passive"))
      (node (ref "C11") (pin "1") (pinfunction "1_1") (pintype "passive"))
      (node (ref "C12") (pin "1") (pinfunction "1_1") (pintype "passive"))
      (node (ref "C13") (pin "1") (pinfunction "1_1") (pintype "passive"))
      (node (ref "C14") (pin "1") (pinfunction "1_1") (pintype "passive"))
      (node (ref "C15") (pin "2") (pinfunction "2_2") (pintype "passive"))
      (node (ref "C16") (pin "2") (pinfunction "2_2") (pintype "passive"))
      (node (ref "C17") (pin "1") (pinfunction "1_1") (pintype "passive"))
      (node (ref "C18") (pin "1") (pinfunction "1_1") (pintype "passive"))
      (node (ref "C19") (pin "2") (pinfunction "2_2") (pintype "passive"))
      (node (ref "C2") (pin "1") (pinfunction "1_1") (pintype "passive"))
      (node (ref "C20") (pin "1") (pinfunction "1_1") (pintype "passive"))
      (node (ref "C21") (pin "1") (pinfunction "1_1") (pintype "passive"))
      (node (ref "C22") (pin "1") (pinfunction "1_1") (pintype "passive"))
      (node (ref "C23") (pin "1") (pinfunction "1_1") (pintype "passive"))
      (node (ref "C24") (pin "2") (pinfunction "2_2") (pintype "passive"))
      (node (ref "C3") (pin "1") (pinfunction "1_1") (pintype "passive"))
      (node (ref "C4") (pin "1") (pinfunction "1_1") (pintype "passive"))
      (node (ref "C5") (pin "1") (pinfunction "1_1") (pintype "passive"))
      (node (ref "C6") (pin "1") (pinfunction "1_1") (pintype "passive"))
      (node (ref "C7") (pin "1") (pinfunction "1_1") (pintype "passive"))
      (node (ref "C8") (pin "1") (pinfunction "1_1") (pintype "passive"))
      (node (ref "C9") (pin "1") (pinfunction "1_1") (pintype "passive"))
      (node (ref "DISPLAY") (pin "GND0") (pinfunction "M_GND_GND0") (pintype "power_in"))
      (node (ref "DISPLAY") (pin "GND1") (pinfunction "M_GND_GND1") (pintype "power_in"))
      (node (ref "DISPLAY") (pin "GND2") (pinfunction "M_GND_GND2") (pintype "power_in"))
      (node (ref "GPS") (pin "10") (pinfunction "GND_10") (pintype "bidirectional"))
      (node (ref "IC1") (pin "11") (pinfunction "PP_11") (pintype "power_in"))
      (node (ref "IC1") (pin "3") (pinfunction "PGND_3") (pintype "power_in"))
      (node (ref "IC1") (pin "9") (pinfunction "GND_9") (pintype "power_in"))
      (node (ref "IC2") (pin "1") (pinfunction "GND_1") (pintype "power_in"))
      (node (ref "IC2") (pin "7") (pinfunction "PP_7") (pintype "power_in"))
      (node (ref "J1") (pin "2") (pinfunction "tip_2") (pintype "bidirectional"))
      (node (ref "J2") (pin "5") (pinfunction "GND_5") (pintype "power_in"))
      (node (ref "PROG") (pin "4") (pinfunction "4_4") (pintype "passive"))
      (node (ref "R20") (pin "2") (pinfunction "2_2") (pintype "passive"))
      (node (ref "R26") (pin "1") (pinfunction "1_1") (pintype "passive"))
      (node (ref "R27") (pin "1") (pinfunction "1_1") (pintype "passive"))
      (node (ref "R6") (pin "1") (pinfunction "1_1") (pintype "passive"))
      (node (ref "S1") (pin "1") (pinfunction "1_1") (pintype "passive"))
      (node (ref "Temp") (pin "2") (pinfunction "GND_2") (pintype "power_in"))
      (node (ref "U1") (pin "14") (pinfunction "AVSS1_14") (pintype "power_in"))
      (node (ref "U1") (pin "19") (pinfunction "DVSS1_19") (pintype "power_in"))
      (node (ref "U1") (pin "49") (pinfunction "DVSS2_49") (pintype "power_in"))
      (node (ref "U1") (pin "61") (pinfunction "VSSU_61") (pintype "power_in"))
      (node (ref "U1") (pin "68") (pinfunction "AVSS2_68") (pintype "power_in"))
      (node (ref "U2") (pin "2") (pinfunction "GND_2") (pintype "power_in"))
      (node (ref "U3") (pin "1") (pinfunction "GND_1") (pintype "power_in"))
      (node (ref "U3") (pin "13") (pinfunction "EP_13") (pintype "power_in"))
      (node (ref "U3") (pin "2") (pinfunction "VM_2") (pintype "input"))
      (node (ref "U4") (pin "4") (pinfunction "GND_4") (pintype "input"))
      (node (ref "U5") (pin "4") (pinfunction "GND_4") (pintype "power_in"))
      (node (ref "U6") (pin "4") (pinfunction "GND_4") (pintype "power_in"))
      (node (ref "U7") (pin "4") (pinfunction "VSS_4") (pintype "power_in"))
      (node (ref "X2") (pin "2") (pinfunction "2_2") (pintype "passive"))
      (node (ref "rf") (pin "1") (pinfunction "GND_1") (pintype "power_in"))
      (node (ref "rf") (pin "11") (pinfunction "GND_11") (pintype "power_in"))
      (node (ref "rf") (pin "13") (pinfunction "GND_13") (pintype "power_in"))
      (node (ref "rf") (pin "22") (pinfunction "GND_22") (pintype "power_in"))
      (node (ref "rf") (pin "35") (pinfunction "GND_35") (pintype "power_in"))
    )
    (net (code "49") (name "Net-(DS1-A)") (class "Default")
      (node (ref "DS1") (pin "1") (pinfunction "A_1") (pintype "passive"))
      (node (ref "R3") (pin "2") (pinfunction "2_2") (pintype "passive"))
    )
    (net (code "50") (name "Net-(DS1-K)") (class "Default")
      (node (ref "DS1") (pin "2") (pinfunction "K_2") (pintype "passive"))
      (node (ref "U2") (pin "3") (pinfunction "~{CHG}_3") (pintype "tri_state"))
    )
    (net (code "51") (name "Net-(GPS-RX)") (class "Default")
      (node (ref "GPS") (pin "3") (pinfunction "RX_3") (pintype "bidirectional"))
      (node (ref "R13") (pin "1") (pinfunction "1_1") (pintype "passive"))
    )
    (net (code "52") (name "Net-(GPS-SCL)") (class "Default")
      (node (ref "GPS") (pin "19") (pinfunction "SCL_19") (pintype "bidirectional"))
      (node (ref "R14") (pin "2") (pinfunction "2_2") (pintype "passive"))
    )
    (net (code "53") (name "Net-(GPS-SDA)") (class "Default")
      (node (ref "GPS") (pin "20") (pinfunction "SDA_20") (pintype "bidirectional"))
      (node (ref "R11") (pin "2") (pinfunction "2_2") (pintype "passive"))
    )
    (net (code "54") (name "Net-(GPS-TX)") (class "Default")
      (node (ref "GPS") (pin "2") (pinfunction "TX_2") (pintype "bidirectional"))
      (node (ref "R12") (pin "1") (pinfunction "1_1") (pintype "passive"))
    )
    (net (code "55") (name "Net-(GPS-VCC)") (class "Default")
      (node (ref "C17") (pin "2") (pinfunction "2_2") (pintype "passive"))
      (node (ref "GPS") (pin "1") (pinfunction "VCC_1") (pintype "bidirectional"))
      (node (ref "L3") (pin "2") (pinfunction "2_2") (pintype "passive"))
    )
    (net (code "56") (name "Net-(IC1-FB)") (class "Default")
      (node (ref "C23") (pin "2") (pinfunction "2_2") (pintype "passive"))
      (node (ref "IC1") (pin "1") (pinfunction "VOUT_1") (pintype "power_in"))
      (node (ref "IC1") (pin "10") (pinfunction "FB_10") (pintype "input"))
      (node (ref "JP3V3") (pin "1") (pinfunction "1_1") (pintype "passive"))
    )
    (net (code "57") (name "Net-(IC1-L1)") (class "Default")
      (node (ref "IC1") (pin "4") (pinfunction "L1_4") (pintype "passive"))
      (node (ref "L1") (pin "1") (pinfunction "1_1") (pintype "passive"))
    )
    (net (code "58") (name "Net-(IC1-L2)") (class "Default")
      (node (ref "IC1") (pin "2") (pinfunction "L2_2") (pintype "passive"))
      (node (ref "L1") (pin "2") (pinfunction "2_2") (pintype "passive"))
    )
    (net (code "59") (name "Net-(IC2-FB)") (class "Default")
      (node (ref "C1") (pin "2") (pinfunction "2_2") (pintype "passive"))
      (node (ref "IC2") (pin "2") (pinfunction "VOUT_2") (pintype "power_in"))
      (node (ref "IC2") (pin "3") (pinfunction "FB_3") (pintype "input"))
      (node (ref "JP5V") (pin "1") (pinfunction "1_1") (pintype "passive"))
    )
    (net (code "60") (name "Net-(IC2-L)") (class "Default")
      (node (ref "IC2") (pin "5") (pinfunction "L_5") (pintype "power_in"))
      (node (ref "L2") (pin "2") (pinfunction "2_2") (pintype "passive"))
    )
    (net (code "61") (name "Net-(R2-Pad1)") (class "Default")
      (node (ref "R2") (pin "1") (pinfunction "1_1") (pintype "passive"))
      (node (ref "R4") (pin "2") (pinfunction "2_2") (pintype "passive"))
    )
    (net (code "62") (name "Net-(R110-Pad2)") (class "Default")
      (node (ref "R110") (pin "2") (pinfunction "2_2") (pintype "passive"))
      (node (ref "R111") (pin "1") (pinfunction "1_1") (pintype "passive"))
    )
    (net (code "63") (name "Net-(R111-Pad2)") (class "Default")
      (node (ref "R111") (pin "2") (pinfunction "2_2") (pintype "passive"))
      (node (ref "R112") (pin "1") (pinfunction "1_1") (pintype "passive"))
    )
    (net (code "64") (name "Net-(U1-P5.4{slash}XIN)") (class "Default")
      (node (ref "C12") (pin "2") (pinfunction "2_2") (pintype "passive"))
      (node (ref "U1") (pin "12") (pinfunction "P5.4/XIN_12") (pintype "bidirectional"))
      (node (ref "X1") (pin "2") (pinfunction "2_2") (pintype "passive"))
    )
    (net (code "65") (name "Net-(U1-P5.5{slash}XOUT)") (class "Default")
      (node (ref "C14") (pin "2") (pinfunction "2_2") (pintype "passive"))
      (node (ref "U1") (pin "13") (pinfunction "P5.5/XOUT_13") (pintype "bidirectional"))
      (node (ref "X1") (pin "1") (pinfunction "1_1") (pintype "passive"))
    )
    (net (code "66") (name "Net-(U1-PUR)") (class "Default")
      (node (ref "R110") (pin "1") (pinfunction "1_1") (pintype "passive"))
      (node (ref "U1") (pin "63") (pinfunction "PUR_63") (pintype "passive"))
    )
    (net (code "67") (name "Net-(U1-TEST{slash}SBWTCK)") (class "Default")
      (node (ref "PROG") (pin "3") (pinfunction "3_3") (pintype "passive"))
      (node (ref "U1") (pin "71") (pinfunction "TEST/SBWTCK_71") (pintype "input"))
    )
    (net (code "68") (name "Net-(U1-V18)") (class "Default")
      (node (ref "C15") (pin "1") (pinfunction "1_1") (pintype "passive"))
      (node (ref "U1") (pin "67") (pinfunction "V18_67") (pintype "passive"))
    )
    (net (code "69") (name "Net-(U1-VCORE)") (class "Default")
      (node (ref "C16") (pin "1") (pinfunction "1_1") (pintype "passive"))
      (node (ref "U1") (pin "20") (pinfunction "VCORE_20") (pintype "passive"))
    )
    (net (code "70") (name "Net-(U1-~{RST}{slash}NMI{slash}SBWTDIO)") (class "Default")
      (node (ref "PROG") (pin "2") (pinfunction "2_2") (pintype "passive"))
      (node (ref "U1") (pin "76") (pinfunction "~{RST}/NMI/SBWTDIO_76") (pintype "bidirectional"))
    )
    (net (code "71") (name "Net-(U3-PDT)") (class "Default")
      (node (ref "C5") (pin "2") (pinfunction "2_2") (pintype "passive"))
      (node (ref "U3") (pin "4") (pinfunction "PDT_4") (pintype "input"))
    )
    (net (code "72") (name "Net-(U3-UVLO)") (class "Default")
      (node (ref "R4") (pin "1") (pinfunction "1_1") (pintype "passive"))
      (node (ref "R5") (pin "2") (pinfunction "2_2") (pintype "passive"))
      (node (ref "U3") (pin "7") (pinfunction "UVLO_7") (pintype "input"))
    )
    (net (code "73") (name "Net-(U3-~{PFI})") (class "Default")
      (node (ref "R5") (pin "1") (pinfunction "1_1") (pintype "passive"))
      (node (ref "R6") (pin "2") (pinfunction "2_2") (pintype "passive"))
      (node (ref "U3") (pin "8") (pinfunction "~{PFI}_8") (pintype "input"))
    )
    (net (code "74") (name "Net-(rf-SPI_CLK{slash}DIO18)") (class "Default")
      (node (ref "R21") (pin "2") (pinfunction "2_2") (pintype "passive"))
      (node (ref "rf") (pin "14") (pinfunction "SPI_CLK/DIO18_14") (pintype "input"))
    )
    (net (code "75") (name "Net-(rf-SPI_MISO{slash}DIO15)") (class "Default")
      (node (ref "R24") (pin "2") (pinfunction "2_2") (pintype "passive"))
      (node (ref "rf") (pin "17") (pinfunction "SPI_MISO/DIO15_17") (pintype "output"))
    )
    (net (code "76") (name "Net-(rf-SPI_MOSI{slash}DIO16)") (class "Default")
      (node (ref "R23") (pin "2") (pinfunction "2_2") (pintype "passive"))
      (node (ref "rf") (pin "16") (pinfunction "SPI_MOSI/DIO16_16") (pintype "input"))
    )
    (net (code "77") (name "Net-(rf-SPI_~{SSEL}{slash}DIO17)") (class "Default")
      (node (ref "R22") (pin "2") (pinfunction "2_2") (pintype "passive"))
      (node (ref "rf") (pin "15") (pinfunction "SPI_~{SSEL}/DIO17_15") (pintype "input"))
    )
    (net (code "78") (name "VCC") (class "Default")
      (node (ref "C11") (pin "2") (pinfunction "2_2") (pintype "passive"))
      (node (ref "C13") (pin "2") (pinfunction "2_2") (pintype "passive"))
      (node (ref "C19") (pin "1") (pinfunction "1_1") (pintype "passive"))
      (node (ref "C20") (pin "2") (pinfunction "2_2") (pintype "passive"))
      (node (ref "C21") (pin "2") (pinfunction "2_2") (pintype "passive"))
      (node (ref "C22") (pin "2") (pinfunction "2_2") (pintype "passive"))
      (node (ref "DISPLAY") (pin "3V3") (pinfunction "3V3_3V3") (pintype "power_in"))
      (node (ref "JP3V3") (pin "2") (pinfunction "2_2") (pintype "passive"))
      (node (ref "L3") (pin "1") (pinfunction "1_1") (pintype "passive"))
      (node (ref "PROG") (pin "1") (pinfunction "1_1") (pintype "passive"))
      (node (ref "R1") (pin "1") (pinfunction "1_1") (pintype "passive"))
      (node (ref "R18") (pin "1") (pinfunction "1_1") (pintype "passive"))
      (node (ref "R19") (pin "2") (pinfunction "2_2") (pintype "passive"))
      (node (ref "R25") (pin "2") (pinfunction "2_2") (pintype "passive"))
      (node (ref "R28") (pin "2") (pinfunction "2_2") (pintype "passive"))
      (node (ref "R29") (pin "2") (pinfunction "2_2") (pintype "passive"))
      (node (ref "R3") (pin "1") (pinfunction "1_1") (pintype "passive"))
      (node (ref "R7") (pin "2") (pinfunction "2_2") (pintype "passive"))
      (node (ref "R9") (pin "2") (pinfunction "2_2") (pintype "passive"))
      (node (ref "Temp") (pin "5") (pinfunction "VDD_5") (pintype "power_in"))
      (node (ref "U1") (pin "11") (pinfunction "AVCC1_11") (pintype "power_in"))
      (node (ref "U1") (pin "18") (pinfunction "DVCC1_18") (pintype "power_in"))
      (node (ref "U1") (pin "50") (pinfunction "DVCC2_50") (pintype "power_in"))
      (node (ref "U1") (pin "66") (pinfunction "VUSB_66") (pintype "power_in"))
      (node (ref "U4") (pin "8") (pinfunction "Vcc_8") (pintype "input"))
      (node (ref "U7") (pin "3") (pinfunction "WP#_3") (pintype "input"))
      (node (ref "U7") (pin "7") (pinfunction "RST#/HOLD#_7") (pintype "input"))
      (node (ref "U7") (pin "8") (pinfunction "VDD_8") (pintype "power_in"))
      (node (ref "rf") (pin "2") (pinfunction "VCC_2") (pintype "power_in"))
    )
    (net (code "79") (name "unconnected-(DISPLAY-M_~{WORD}_STOCK_CS-PadD9)") (class "Default")
      (node (ref "DISPLAY") (pin "D9") (pinfunction "M_~{WORD}_STOCK_CS_D9") (pintype "bidirectional"))
    )
    (net (code "80") (name "unconnected-(DISPLAY-nc-Pad5V)") (class "Default")
      (node (ref "DISPLAY") (pin "5V") (pinfunction "nc_5V") (pintype "passive"))
    )
    (net (code "81") (name "unconnected-(DISPLAY-nc-PadA5)") (class "Default")
      (node (ref "DISPLAY") (pin "A5") (pinfunction "nc_A5") (pintype "passive"))
    )
    (net (code "82") (name "unconnected-(DISPLAY-nc-PadNC0)") (class "Default")
      (node (ref "DISPLAY") (pin "NC0") (pinfunction "nc_NC0") (pintype "passive"))
    )
    (net (code "83") (name "unconnected-(DISPLAY-nc-PadNC1)") (class "Default")
      (node (ref "DISPLAY") (pin "NC1") (pinfunction "nc_NC1") (pintype "passive"))
    )
    (net (code "84") (name "unconnected-(DISPLAY-nc-PadRST)") (class "Default")
      (node (ref "DISPLAY") (pin "RST") (pinfunction "nc_RST") (pintype "passive"))
    )
    (net (code "85") (name "unconnected-(DISPLAY-nc-PadVIN)") (class "Default")
      (node (ref "DISPLAY") (pin "VIN") (pinfunction "nc_VIN") (pintype "passive"))
    )
    (net (code "86") (name "unconnected-(GPS-EX-Pad5)") (class "Default")
      (node (ref "GPS") (pin "5") (pinfunction "EX_5") (pintype "bidirectional"))
    )
    (net (code "87") (name "unconnected-(GPS-NC-Pad4)") (class "Default")
      (node (ref "GPS") (pin "4") (pinfunction "NC_4") (pintype "bidirectional"))
    )
    (net (code "88") (name "unconnected-(GPS-NC-Pad6)") (class "Default")
      (node (ref "GPS") (pin "6") (pinfunction "NC_6") (pintype "bidirectional"))
    )
    (net (code "89") (name "unconnected-(GPS-NC-Pad7)") (class "Default")
      (node (ref "GPS") (pin "7") (pinfunction "NC_7") (pintype "bidirectional"))
    )
    (net (code "90") (name "unconnected-(GPS-NC-Pad8)") (class "Default")
      (node (ref "GPS") (pin "8") (pinfunction "NC_8") (pintype "bidirectional"))
    )
    (net (code "91") (name "unconnected-(GPS-NC-Pad9)") (class "Default")
      (node (ref "GPS") (pin "9") (pinfunction "NC_9") (pintype "bidirectional"))
    )
    (net (code "92") (name "unconnected-(GPS-NC-Pad11)") (class "Default")
      (node (ref "GPS") (pin "11") (pinfunction "NC_11") (pintype "bidirectional"))
    )
    (net (code "93") (name "unconnected-(GPS-NC-Pad12)") (class "Default")
      (node (ref "GPS") (pin "12") (pinfunction "NC_12") (pintype "bidirectional"))
    )
    (net (code "94") (name "unconnected-(GPS-NC-Pad13)") (class "Default")
      (node (ref "GPS") (pin "13") (pinfunction "NC_13") (pintype "bidirectional"))
    )
    (net (code "95") (name "unconnected-(GPS-NC-Pad14)") (class "Default")
      (node (ref "GPS") (pin "14") (pinfunction "NC_14") (pintype "bidirectional"))
    )
    (net (code "96") (name "unconnected-(GPS-NC-Pad16)") (class "Default")
      (node (ref "GPS") (pin "16") (pinfunction "NC_16") (pintype "bidirectional"))
    )
    (net (code "97") (name "unconnected-(GPS-NC-Pad17)") (class "Default")
      (node (ref "GPS") (pin "17") (pinfunction "NC_17") (pintype "bidirectional"))
    )
    (net (code "98") (name "unconnected-(GPS-NC-Pad18)") (class "Default")
      (node (ref "GPS") (pin "18") (pinfunction "NC_18") (pintype "bidirectional"))
    )
    (net (code "99") (name "unconnected-(GPS-TP-Pad15)") (class "Default")
      (node (ref "GPS") (pin "15") (pinfunction "TP_15") (pintype "bidirectional"))
    )
    (net (code "100") (name "unconnected-(J1-ring_1_switch-Pad6)") (class "Default")
      (node (ref "J1") (pin "6") (pinfunction "ring_1_switch_6") (pintype "bidirectional"))
    )
    (net (code "101") (name "unconnected-(J2-ID-Pad4)") (class "Default")
      (node (ref "J2") (pin "4") (pinfunction "ID_4") (pintype "passive"))
    )
    (net (code "102") (name "unconnected-(Temp-nc-Pad3)") (class "Default")
      (node (ref "Temp") (pin "3") (pinfunction "nc_3") (pintype "passive"))
    )
    (net (code "103") (name "unconnected-(Temp-nc-Pad4)") (class "Default")
      (node (ref "Temp") (pin "4") (pinfunction "nc_4") (pintype "passive"))
    )
    (net (code "104") (name "unconnected-(U1-P2.2{slash}TA2CLK{slash}SMCLK-Pad31)") (class "Default")
      (node (ref "U1") (pin "31") (pinfunction "P2.2/TA2CLK/SMCLK_31") (pintype "bidirectional"))
    )
    (net (code "105") (name "unconnected-(U1-P2.4{slash}TA2.1-Pad33)") (class "Default")
      (node (ref "U1") (pin "33") (pinfunction "P2.4/TA2.1_33") (pintype "bidirectional"))
    )
    (net (code "106") (name "unconnected-(U1-P2.5{slash}TA2.2-Pad34)") (class "Default")
      (node (ref "U1") (pin "34") (pinfunction "P2.5/TA2.2_34") (pintype "bidirectional"))
    )
    (net (code "107") (name "unconnected-(U1-P3.2{slash}UCB0CLK{slash}UCA0STE-Pad39)") (class "Default")
      (node (ref "U1") (pin "39") (pinfunction "P3.2/UCB0CLK/UCA0STE_39") (pintype "bidirectional"))
    )
    (net (code "108") (name "unconnected-(U1-P4.7{slash}PM_NONE-Pad54)") (class "Default")
      (node (ref "U1") (pin "54") (pinfunction "P4.7/PM_NONE_54") (pintype "bidirectional"))
    )
    (net (code "109") (name "unconnected-(U1-P5.0{slash}A8{slash}VREF+{slash}VEREF+-Pad9)") (class "Default")
      (node (ref "U1") (pin "9") (pinfunction "P5.0/A8/VREF+/VEREF+_9") (pintype "bidirectional"))
    )
    (net (code "110") (name "unconnected-(U1-P5.1{slash}A9{slash}VREF-{slash}VEREF--Pad10)") (class "Default")
      (node (ref "U1") (pin "10") (pinfunction "P5.1/A9/VREF-/VEREF-_10") (pintype "bidirectional"))
    )
    (net (code "111") (name "unconnected-(U1-P5.6{slash}TB0.0-Pad55)") (class "Default")
      (node (ref "U1") (pin "55") (pinfunction "P5.6/TB0.0_55") (pintype "bidirectional"))
    )
    (net (code "112") (name "unconnected-(U1-P5.7{slash}TB0.1-Pad56)") (class "Default")
      (node (ref "U1") (pin "56") (pinfunction "P5.7/TB0.1_56") (pintype "bidirectional"))
    )
    (net (code "113") (name "unconnected-(U1-P6.1{slash}CB1{slash}A1-Pad78)") (class "Default")
      (node (ref "U1") (pin "78") (pinfunction "P6.1/CB1/A1_78") (pintype "bidirectional"))
    )
    (net (code "114") (name "unconnected-(U1-P6.2{slash}CB2{slash}A2-Pad79)") (class "Default")
      (node (ref "U1") (pin "79") (pinfunction "P6.2/CB2/A2_79") (pintype "bidirectional"))
    )
    (net (code "115") (name "unconnected-(U1-P6.3{slash}CB3{slash}A3-Pad80)") (class "Default")
      (node (ref "U1") (pin "80") (pinfunction "P6.3/CB3/A3_80") (pintype "bidirectional"))
    )
    (net (code "116") (name "unconnected-(U1-P6.4{slash}CB4{slash}A4-Pad1)") (class "Default")
      (node (ref "U1") (pin "1") (pinfunction "P6.4/CB4/A4_1") (pintype "bidirectional"))
    )
    (net (code "117") (name "unconnected-(U1-P6.7{slash}CB7{slash}A7-Pad4)") (class "Default")
      (node (ref "U1") (pin "4") (pinfunction "P6.7/CB7/A7_4") (pintype "bidirectional"))
    )
    (net (code "118") (name "unconnected-(U1-P7.0{slash}CB8{slash}A12-Pad5)") (class "Default")
      (node (ref "U1") (pin "5") (pinfunction "P7.0/CB8/A12_5") (pintype "bidirectional"))
    )
    (net (code "119") (name "unconnected-(U1-P7.3{slash}CB11{slash}A15-Pad8)") (class "Default")
      (node (ref "U1") (pin "8") (pinfunction "P7.3/CB11/A15_8") (pintype "bidirectional"))
    )
    (net (code "120") (name "unconnected-(U1-P7.4{slash}TB0.2-Pad57)") (class "Default")
      (node (ref "U1") (pin "57") (pinfunction "P7.4/TB0.2_57") (pintype "bidirectional"))
    )
    (net (code "121") (name "unconnected-(U1-P7.5{slash}TB0.3-Pad58)") (class "Default")
      (node (ref "U1") (pin "58") (pinfunction "P7.5/TB0.3_58") (pintype "bidirectional"))
    )
    (net (code "122") (name "unconnected-(U1-P7.6{slash}TB0.4-Pad59)") (class "Default")
      (node (ref "U1") (pin "59") (pinfunction "P7.6/TB0.4_59") (pintype "bidirectional"))
    )
    (net (code "123") (name "unconnected-(U1-P7.7{slash}TB0CLK{slash}MCLK-Pad60)") (class "Default")
      (node (ref "U1") (pin "60") (pinfunction "P7.7/TB0CLK/MCLK_60") (pintype "bidirectional"))
    )
    (net (code "124") (name "unconnected-(U1-P8.0-Pad15)") (class "Default")
      (node (ref "U1") (pin "15") (pinfunction "P8.0_15") (pintype "bidirectional"))
    )
    (net (code "125") (name "unconnected-(U1-P8.2-Pad17)") (class "Default")
      (node (ref "U1") (pin "17") (pinfunction "P8.2_17") (pintype "bidirectional"))
    )
    (net (code "126") (name "unconnected-(U1-PJ.0{slash}TDO-Pad72)") (class "Default")
      (node (ref "U1") (pin "72") (pinfunction "PJ.0/TDO_72") (pintype "bidirectional"))
    )
    (net (code "127") (name "unconnected-(U1-PJ.1{slash}TDI{slash}TCLK-Pad73)") (class "Default")
      (node (ref "U1") (pin "73") (pinfunction "PJ.1/TDI/TCLK_73") (pintype "bidirectional"))
    )
    (net (code "128") (name "unconnected-(U1-PJ.2{slash}TMS-Pad74)") (class "Default")
      (node (ref "U1") (pin "74") (pinfunction "PJ.2/TMS_74") (pintype "bidirectional"))
    )
    (net (code "129") (name "unconnected-(U1-PJ.3{slash}TCK-Pad75)") (class "Default")
      (node (ref "U1") (pin "75") (pinfunction "PJ.3/TCK_75") (pintype "bidirectional"))
    )
    (net (code "130") (name "unconnected-(U2-DC-Pad4)") (class "Default")
      (node (ref "U2") (pin "4") (pinfunction "DC_4") (pintype "power_in"))
    )
    (net (code "131") (name "unconnected-(U3-~{RST}-Pad10)") (class "Default")
      (node (ref "U3") (pin "10") (pinfunction "~{RST}_10") (pintype "open_collector"))
    )
    (net (code "132") (name "unconnected-(U4-nc-Pad1)") (class "Default")
      (node (ref "U4") (pin "1") (pinfunction "nc_1") (pintype "passive"))
    )
    (net (code "133") (name "unconnected-(U5-NC-Pad2)") (class "Default")
      (node (ref "U5") (pin "2") (pinfunction "NC_2") (pintype "passive"))
    )
    (net (code "134") (name "unconnected-(U5-NC-Pad5)") (class "Default")
      (node (ref "U5") (pin "5") (pinfunction "NC_5") (pintype "passive"))
    )
    (net (code "135") (name "unconnected-(U6-NC-Pad2)") (class "Default")
      (node (ref "U6") (pin "2") (pinfunction "NC_2") (pintype "passive"))
    )
    (net (code "136") (name "unconnected-(U6-NC-Pad5)") (class "Default")
      (node (ref "U6") (pin "5") (pinfunction "NC_5") (pintype "passive"))
    )
    (net (code "137") (name "unconnected-(rf-AD0{slash}DIO0-Pad33)") (class "Default")
      (node (ref "rf") (pin "33") (pinfunction "AD0/DIO0_33") (pintype "input"))
    )
    (net (code "138") (name "unconnected-(rf-AD1{slash}DIO1-Pad32)") (class "Default")
      (node (ref "rf") (pin "32") (pinfunction "AD1/DIO1_32") (pintype "passive"))
    )
    (net (code "139") (name "unconnected-(rf-AD2{slash}DIO2-Pad31)") (class "Default")
      (node (ref "rf") (pin "31") (pinfunction "AD2/DIO2_31") (pintype "passive"))
    )
    (net (code "140") (name "unconnected-(rf-AD3{slash}DIO3-Pad30)") (class "Default")
      (node (ref "rf") (pin "30") (pinfunction "AD3/DIO3_30") (pintype "passive"))
    )
    (net (code "141") (name "unconnected-(rf-ASSOCIATE{slash}DIO5-Pad28)") (class "Default")
      (node (ref "rf") (pin "28") (pinfunction "ASSOCIATE/DIO5_28") (pintype "output"))
    )
    (net (code "142") (name "unconnected-(rf-DIO4-Pad24)") (class "Default")
      (node (ref "rf") (pin "24") (pinfunction "DIO4_24") (pintype "passive"))
    )
    (net (code "143") (name "unconnected-(rf-DIO12-Pad5)") (class "Default")
      (node (ref "rf") (pin "5") (pinfunction "DIO12_5") (pintype "bidirectional"))
    )
    (net (code "144") (name "unconnected-(rf-ON{slash}~{SLEEP}{slash}DIO9-Pad26)") (class "Default")
      (node (ref "rf") (pin "26") (pinfunction "ON/~{SLEEP}/DIO9_26") (pintype "output"))
    )
    (net (code "145") (name "unconnected-(rf-PWM1_{slash}_DIO11-Pad8)") (class "Default")
      (node (ref "rf") (pin "8") (pinfunction "PWM1_/_DIO11_8") (pintype "passive"))
    )
    (net (code "146") (name "unconnected-(rf-RF-Pad36)") (class "Default")
      (node (ref "rf") (pin "36") (pinfunction "RF_36") (pintype "bidirectional"))
    )
    (net (code "147") (name "unconnected-(rf-RSSI_PWM_{slash}_DIO10-Pad7)") (class "Default")
      (node (ref "rf") (pin "7") (pinfunction "RSSI_PWM_/_DIO10_7") (pintype "output"))
    )
    (net (code "148") (name "unconnected-(rf-SPI_~{ATTN}{slash}~{BOOTMOD}E{slash}DIO19-Pad12)") (class "Default")
      (node (ref "rf") (pin "12") (pinfunction "SPI_~{ATTN}/~{BOOTMOD}E/DIO19_12") (pintype "output"))
    )
    (net (code "149") (name "unconnected-(rf-VREF-Pad27)") (class "Default")
      (node (ref "rf") (pin "27") (pinfunction "VREF_27") (pintype "power_in"))
    )
    (net (code "150") (name "unconnected-(rf-reserved-Pad9)") (class "Default")
      (node (ref "rf") (pin "9") (pinfunction "reserved_9") (pintype "passive"))
    )
    (net (code "151") (name "unconnected-(rf-reserved-Pad18)") (class "Default")
      (node (ref "rf") (pin "18") (pinfunction "reserved_18") (pintype "passive"))
    )
    (net (code "152") (name "unconnected-(rf-reserved-Pad19)") (class "Default")
      (node (ref "rf") (pin "19") (pinfunction "reserved_19") (pintype "passive"))
    )
    (net (code "153") (name "unconnected-(rf-reserved-Pad20)") (class "Default")
      (node (ref "rf") (pin "20") (pinfunction "reserved_20") (pintype "passive"))
    )
    (net (code "154") (name "unconnected-(rf-reserved-Pad21)") (class "Default")
      (node (ref "rf") (pin "21") (pinfunction "reserved_21") (pintype "passive"))
    )
    (net (code "155") (name "unconnected-(rf-reserved-Pad23)") (class "Default")
      (node (ref "rf") (pin "23") (pinfunction "reserved_23") (pintype "passive"))
    )
    (net (code "156") (name "unconnected-(rf-reserved-Pad34)") (class "Default")
      (node (ref "rf") (pin "34") (pinfunction "reserved_34") (pintype "passive"))
    )
    (net (code "157") (name "unconnected-(rf-reserved-Pad37)") (class "Default")
      (node (ref "rf") (pin "37") (pinfunction "reserved_37") (pintype "passive"))
    )
    (net (code "158") (name "unconnected-(rf-~{CTS}{slash}DIO7-Pad25)") (class "Default")
      (node (ref "rf") (pin "25") (pinfunction "~{CTS}/DIO7_25") (pintype "output"))
    )
  )
)
